# busfahrer.net
KiCad netlist of a schematic drawn in EAGLE
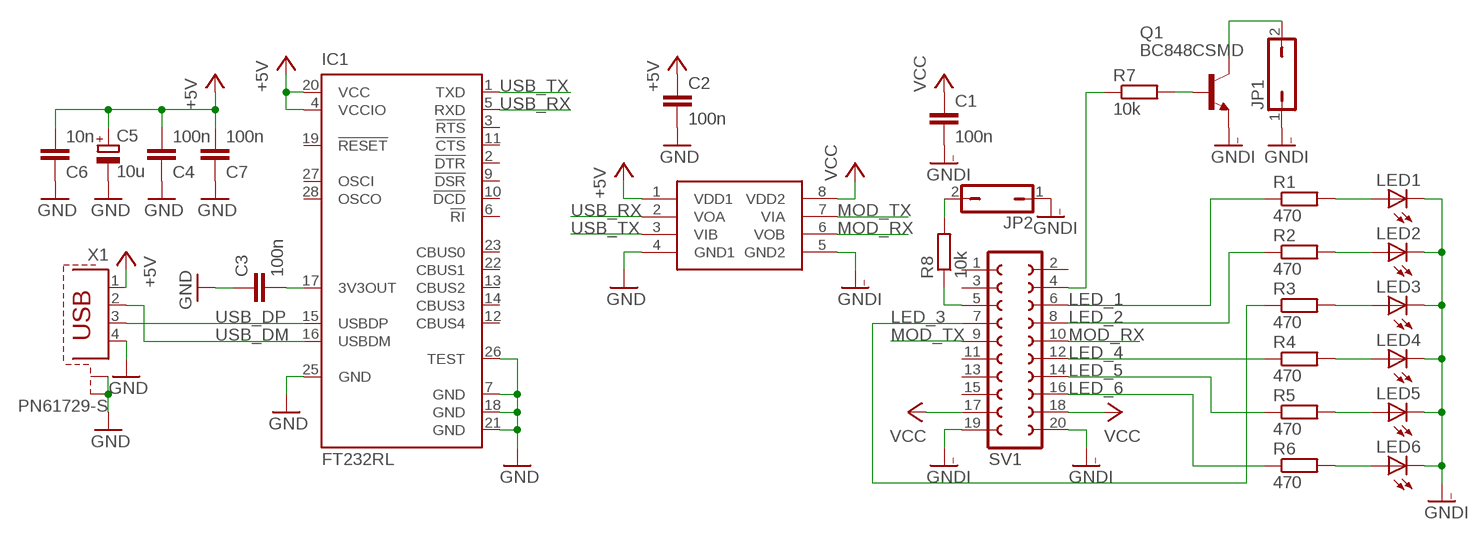
[diagram p0: schematic, sheet 1]

(export (version "E")
  (design (tool "Eeschema 10.0.6"))
  (components
    (comp (ref "C1")
      (value "100n")
      (footprint "eagle-import:C0805")
      (libsource (lib "eagle-import") (part "C-EUC0805"))
    )
    (comp (ref "C2")
      (value "100n")
      (footprint "eagle-import:C0805")
      (libsource (lib "eagle-import") (part "C-EUC0805"))
    )
    (comp (ref "C3")
      (value "100n")
      (footprint "eagle-import:C0805")
      (libsource (lib "eagle-import") (part "C-EUC0805"))
    )
    (comp (ref "C4")
      (value "100n")
      (footprint "eagle-import:C0805")
      (libsource (lib "eagle-import") (part "C-EUC0805"))
    )
    (comp (ref "C5")
      (value "10u")
      (footprint "eagle-import:E1,8-4")
      (libsource (lib "eagle-import") (part "CPOL-EUE1.8-4"))
    )
    (comp (ref "C6")
      (value "10n")
      (footprint "eagle-import:C0805")
      (libsource (lib "eagle-import") (part "C-EUC0805"))
    )
    (comp (ref "C7")
      (value "100n")
      (footprint "eagle-import:C0805")
      (libsource (lib "eagle-import") (part "C-EUC0805"))
    )
    (comp (ref "IC1")
      (value "FT232RL")
      (footprint "eagle-import:SSOP28")
      (libsource (lib "eagle-import") (part "FT232RL"))
    )
    (comp (ref "JP1")
      (value "JP1Q")
      (footprint "eagle-import:JP1")
      (libsource (lib "eagle-import") (part "JP1Q"))
    )
    (comp (ref "JP2")
      (value "JP1Q")
      (footprint "eagle-import:JP1")
      (libsource (lib "eagle-import") (part "JP1Q"))
    )
    (comp (ref "LED1")
      (value "LEDCHIPLED_0805")
      (footprint "eagle-import:CHIPLED_0805")
      (libsource (lib "eagle-import") (part "LEDCHIPLED_0805"))
    )
    (comp (ref "LED2")
      (value "LEDCHIPLED_0805")
      (footprint "eagle-import:CHIPLED_0805")
      (libsource (lib "eagle-import") (part "LEDCHIPLED_0805"))
    )
    (comp (ref "LED3")
      (value "LEDCHIPLED_0805")
      (footprint "eagle-import:CHIPLED_0805")
      (libsource (lib "eagle-import") (part "LEDCHIPLED_0805"))
    )
    (comp (ref "LED4")
      (value "LEDCHIPLED_0805")
      (footprint "eagle-import:CHIPLED_0805")
      (libsource (lib "eagle-import") (part "LEDCHIPLED_0805"))
    )
    (comp (ref "LED5")
      (value "LEDCHIPLED_0805")
      (footprint "eagle-import:CHIPLED_0805")
      (libsource (lib "eagle-import") (part "LEDCHIPLED_0805"))
    )
    (comp (ref "LED6")
      (value "LEDCHIPLED_0805")
      (footprint "eagle-import:CHIPLED_0805")
      (libsource (lib "eagle-import") (part "LEDCHIPLED_0805"))
    )
    (comp (ref "Q1")
      (value "BC848CSMD")
      (footprint "eagle-import:SOT23")
      (libsource (lib "eagle-import") (part "BC848SMDC"))
    )
    (comp (ref "R1")
      (value "470")
      (footprint "eagle-import:R0805")
      (libsource (lib "eagle-import") (part "R-EU_R0805"))
    )
    (comp (ref "R2")
      (value "470")
      (footprint "eagle-import:R0805")
      (libsource (lib "eagle-import") (part "R-EU_R0805"))
    )
    (comp (ref "R3")
      (value "470")
      (footprint "eagle-import:R0805")
      (libsource (lib "eagle-import") (part "R-EU_R0805"))
    )
    (comp (ref "R4")
      (value "470")
      (footprint "eagle-import:R0805")
      (libsource (lib "eagle-import") (part "R-EU_R0805"))
    )
    (comp (ref "R5")
      (value "470")
      (footprint "eagle-import:R0805")
      (libsource (lib "eagle-import") (part "R-EU_R0805"))
    )
    (comp (ref "R6")
      (value "470")
      (footprint "eagle-import:R0805")
      (libsource (lib "eagle-import") (part "R-EU_R0805"))
    )
    (comp (ref "R7")
      (value "10k")
      (footprint "eagle-import:R0805")
      (libsource (lib "eagle-import") (part "R-EU_R0805"))
    )
    (comp (ref "R8")
      (value "10k")
      (footprint "eagle-import:R0805")
      (libsource (lib "eagle-import") (part "R-EU_R0805"))
    )
    (comp (ref "SV1")
      (value "FE10-2")
      (footprint "eagle-import:FE10-2")
      (libsource (lib "eagle-import") (part "FE10-2"))
    )
    (comp (ref "U$1")
      (value "ADUM3211")
      (footprint "eagle-import:SO8")
      (libsource (lib "eagle-import") (part "ADUM3211"))
    )
    (comp (ref "X1")
      (value "PN61729-S")
      (footprint "eagle-import:PN61729-S")
      (libsource (lib "eagle-import") (part "PN61729-S"))
    )
  )
  (nets
    (net (code "1") (name "+5V") (class "Default")
      (node (ref "C2") (pin "1") (pinfunction "1_1") (pintype "passive"))
      (node (ref "C4") (pin "2") (pinfunction "2_2") (pintype "passive"))
      (node (ref "C5") (pin "+") (pinfunction "+_+") (pintype "passive"))
      (node (ref "C6") (pin "2") (pinfunction "2_2") (pintype "passive"))
      (node (ref "C7") (pin "2") (pinfunction "2_2") (pintype "passive"))
      (node (ref "IC1") (pin "20") (pinfunction "VCC_20") (pintype "power_in"))
      (node (ref "IC1") (pin "4") (pinfunction "VCCIO_4") (pintype "power_in"))
      (node (ref "U$1") (pin "1") (pinfunction "VDD1_1") (pintype "bidirectional"))
      (node (ref "X1") (pin "1") (pinfunction "1_1") (pintype "passive"))
    )
    (net (code "2") (name "/LED_1") (class "Default")
      (node (ref "R1") (pin "1") (pinfunction "1_1") (pintype "passive"))
      (node (ref "SV1") (pin "6") (pinfunction "6_6") (pintype "passive"))
    )
    (net (code "3") (name "/LED_2") (class "Default")
      (node (ref "R2") (pin "1") (pinfunction "1_1") (pintype "passive"))
      (node (ref "SV1") (pin "8") (pinfunction "8_8") (pintype "passive"))
    )
    (net (code "4") (name "/LED_3") (class "Default")
      (node (ref "R3") (pin "1") (pinfunction "1_1") (pintype "passive"))
      (node (ref "SV1") (pin "7") (pinfunction "7_7") (pintype "passive"))
    )
    (net (code "5") (name "/LED_4") (class "Default")
      (node (ref "R4") (pin "1") (pinfunction "1_1") (pintype "passive"))
      (node (ref "SV1") (pin "12") (pinfunction "12_12") (pintype "passive"))
    )
    (net (code "6") (name "/LED_5") (class "Default")
      (node (ref "R5") (pin "1") (pinfunction "1_1") (pintype "passive"))
      (node (ref "SV1") (pin "14") (pinfunction "14_14") (pintype "passive"))
    )
    (net (code "7") (name "/LED_6") (class "Default")
      (node (ref "R6") (pin "1") (pinfunction "1_1") (pintype "passive"))
      (node (ref "SV1") (pin "16") (pinfunction "16_16") (pintype "passive"))
    )
    (net (code "8") (name "/MOD_RX") (class "Default")
      (node (ref "SV1") (pin "10") (pinfunction "10_10") (pintype "passive"))
      (node (ref "U$1") (pin "6") (pinfunction "VOB_6") (pintype "bidirectional"))
    )
    (net (code "9") (name "/MOD_TX") (class "Default")
      (node (ref "SV1") (pin "9") (pinfunction "9_9") (pintype "passive"))
      (node (ref "U$1") (pin "7") (pinfunction "VIA_7") (pintype "bidirectional"))
    )
    (net (code "10") (name "/USB_DM") (class "Default")
      (node (ref "IC1") (pin "16") (pinfunction "USBDM_16") (pintype "bidirectional"))
      (node (ref "X1") (pin "2") (pinfunction "2_2") (pintype "passive"))
    )
    (net (code "11") (name "/USB_DP") (class "Default")
      (node (ref "IC1") (pin "15") (pinfunction "USBDP_15") (pintype "bidirectional"))
      (node (ref "X1") (pin "3") (pinfunction "3_3") (pintype "passive"))
    )
    (net (code "12") (name "/USB_RX") (class "Default")
      (node (ref "IC1") (pin "5") (pinfunction "RXD_5") (pintype "input"))
      (node (ref "U$1") (pin "2") (pinfunction "VOA_2") (pintype "bidirectional"))
    )
    (net (code "13") (name "/USB_TX") (class "Default")
      (node (ref "IC1") (pin "1") (pinfunction "TXD_1") (pintype "output"))
      (node (ref "U$1") (pin "3") (pinfunction "VIB_3") (pintype "bidirectional"))
    )
    (net (code "14") (name "GND") (class "Default")
      (node (ref "C2") (pin "2") (pinfunction "2_2") (pintype "passive"))
      (node (ref "C3") (pin "1") (pinfunction "1_1") (pintype "passive"))
      (node (ref "C4") (pin "1") (pinfunction "1_1") (pintype "passive"))
      (node (ref "C5") (pin "-") (pinfunction "-_-") (pintype "passive"))
      (node (ref "C6") (pin "1") (pinfunction "1_1") (pintype "passive"))
      (node (ref "C7") (pin "1") (pinfunction "1_1") (pintype "passive"))
      (node (ref "IC1") (pin "18") (pinfunction "GND_18") (pintype "power_in"))
      (node (ref "IC1") (pin "21") (pinfunction "GND_21") (pintype "power_in"))
      (node (ref "IC1") (pin "25") (pinfunction "GND_25") (pintype "power_in"))
      (node (ref "IC1") (pin "26") (pinfunction "TEST_26") (pintype "input"))
      (node (ref "IC1") (pin "7") (pinfunction "GND_7") (pintype "power_in"))
      (node (ref "U$1") (pin "4") (pinfunction "GND1_4") (pintype "bidirectional"))
      (node (ref "X1") (pin "4") (pinfunction "4_4") (pintype "passive"))
      (node (ref "X1") (pin "S1") (pinfunction "S1_S1") (pintype "passive"))
      (node (ref "X1") (pin "S2") (pinfunction "S2_S2") (pintype "passive"))
    )
    (net (code "15") (name "GNDI") (class "Default")
      (node (ref "C1") (pin "2") (pinfunction "2_2") (pintype "passive"))
      (node (ref "JP1") (pin "1") (pinfunction "1_1") (pintype "passive"))
      (node (ref "JP2") (pin "1") (pinfunction "1_1") (pintype "passive"))
      (node (ref "LED1") (pin "C") (pinfunction "C_C") (pintype "passive"))
      (node (ref "LED2") (pin "C") (pinfunction "C_C") (pintype "passive"))
      (node (ref "LED3") (pin "C") (pinfunction "C_C") (pintype "passive"))
      (node (ref "LED4") (pin "C") (pinfunction "C_C") (pintype "passive"))
      (node (ref "LED5") (pin "C") (pinfunction "C_C") (pintype "passive"))
      (node (ref "LED6") (pin "C") (pinfunction "C_C") (pintype "passive"))
      (node (ref "Q1") (pin "2") (pinfunction "E_2") (pintype "passive"))
      (node (ref "SV1") (pin "19") (pinfunction "19_19") (pintype "passive"))
      (node (ref "SV1") (pin "20") (pinfunction "20_20") (pintype "passive"))
      (node (ref "U$1") (pin "5") (pinfunction "GND2_5") (pintype "bidirectional"))
    )
    (net (code "16") (name "Net-(IC1-3V3OUT)") (class "Default")
      (node (ref "C3") (pin "2") (pinfunction "2_2") (pintype "passive"))
      (node (ref "IC1") (pin "17") (pinfunction "3V3OUT_17") (pintype "output"))
    )
    (net (code "17") (name "Net-(JP2-Pad2)") (class "Default")
      (node (ref "JP2") (pin "2") (pinfunction "2_2") (pintype "passive"))
      (node (ref "R8") (pin "2") (pinfunction "2_2") (pintype "passive"))
    )
    (net (code "18") (name "Net-(LED1-PadA)") (class "Default")
      (node (ref "LED1") (pin "A") (pinfunction "A_A") (pintype "passive"))
      (node (ref "R1") (pin "2") (pinfunction "2_2") (pintype "passive"))
    )
    (net (code "19") (name "Net-(LED2-PadA)") (class "Default")
      (node (ref "LED2") (pin "A") (pinfunction "A_A") (pintype "passive"))
      (node (ref "R2") (pin "2") (pinfunction "2_2") (pintype "passive"))
    )
    (net (code "20") (name "Net-(LED3-PadA)") (class "Default")
      (node (ref "LED3") (pin "A") (pinfunction "A_A") (pintype "passive"))
      (node (ref "R3") (pin "2") (pinfunction "2_2") (pintype "passive"))
    )
    (net (code "21") (name "Net-(LED4-PadA)") (class "Default")
      (node (ref "LED4") (pin "A") (pinfunction "A_A") (pintype "passive"))
      (node (ref "R4") (pin "2") (pinfunction "2_2") (pintype "passive"))
    )
    (net (code "22") (name "Net-(LED5-PadA)") (class "Default")
      (node (ref "LED5") (pin "A") (pinfunction "A_A") (pintype "passive"))
      (node (ref "R5") (pin "2") (pinfunction "2_2") (pintype "passive"))
    )
    (net (code "23") (name "Net-(LED6-PadA)") (class "Default")
      (node (ref "LED6") (pin "A") (pinfunction "A_A") (pintype "passive"))
      (node (ref "R6") (pin "2") (pinfunction "2_2") (pintype "passive"))
    )
    (net (code "24") (name "Net-(Q1-B)") (class "Default")
      (node (ref "Q1") (pin "1") (pinfunction "B_1") (pintype "passive"))
      (node (ref "R7") (pin "2") (pinfunction "2_2") (pintype "passive"))
    )
    (net (code "25") (name "Net-(Q1-C)") (class "Default")
      (node (ref "JP1") (pin "2") (pinfunction "2_2") (pintype "passive"))
      (node (ref "Q1") (pin "3") (pinfunction "C_3") (pintype "passive"))
    )
    (net (code "26") (name "Net-(R7-Pad1)") (class "Default")
      (node (ref "R7") (pin "1") (pinfunction "1_1") (pintype "passive"))
      (node (ref "SV1") (pin "4") (pinfunction "4_4") (pintype "passive"))
    )
    (net (code "27") (name "Net-(R8-Pad1)") (class "Default")
      (node (ref "R8") (pin "1") (pinfunction "1_1") (pintype "passive"))
      (node (ref "SV1") (pin "5") (pinfunction "5_5") (pintype "passive"))
    )
    (net (code "28") (name "VCC") (class "Default")
      (node (ref "C1") (pin "1") (pinfunction "1_1") (pintype "passive"))
      (node (ref "SV1") (pin "17") (pinfunction "17_17") (pintype "passive"))
      (node (ref "SV1") (pin "18") (pinfunction "18_18") (pintype "passive"))
      (node (ref "U$1") (pin "8") (pinfunction "VDD2_8") (pintype "bidirectional"))
    )
    (net (code "29") (name "unconnected-(IC1-CBUS0-Pad23)") (class "Default")
      (node (ref "IC1") (pin "23") (pinfunction "CBUS0_23") (pintype "bidirectional"))
    )
    (net (code "30") (name "unconnected-(IC1-CBUS1-Pad22)") (class "Default")
      (node (ref "IC1") (pin "22") (pinfunction "CBUS1_22") (pintype "bidirectional"))
    )
    (net (code "31") (name "unconnected-(IC1-CBUS2-Pad13)") (class "Default")
      (node (ref "IC1") (pin "13") (pinfunction "CBUS2_13") (pintype "bidirectional"))
    )
    (net (code "32") (name "unconnected-(IC1-CBUS3-Pad14)") (class "Default")
      (node (ref "IC1") (pin "14") (pinfunction "CBUS3_14") (pintype "bidirectional"))
    )
    (net (code "33") (name "unconnected-(IC1-CBUS4-Pad12)") (class "Default")
      (node (ref "IC1") (pin "12") (pinfunction "CBUS4_12") (pintype "bidirectional"))
    )
    (net (code "34") (name "unconnected-(IC1-OSCI-Pad27)") (class "Default")
      (node (ref "IC1") (pin "27") (pinfunction "OSCI_27") (pintype "input"))
    )
    (net (code "35") (name "unconnected-(IC1-OSCO-Pad28)") (class "Default")
      (node (ref "IC1") (pin "28") (pinfunction "OSCO_28") (pintype "output"))
    )
    (net (code "36") (name "unconnected-(IC1-~{CTS}-Pad11)") (class "Default")
      (node (ref "IC1") (pin "11") (pinfunction "~{CTS}_11") (pintype "input"))
    )
    (net (code "37") (name "unconnected-(IC1-~{DCD}-Pad10)") (class "Default")
      (node (ref "IC1") (pin "10") (pinfunction "~{DCD}_10") (pintype "input"))
    )
    (net (code "38") (name "unconnected-(IC1-~{DSR}-Pad9)") (class "Default")
      (node (ref "IC1") (pin "9") (pinfunction "~{DSR}_9") (pintype "input"))
    )
    (net (code "39") (name "unconnected-(IC1-~{DTR}-Pad2)") (class "Default")
      (node (ref "IC1") (pin "2") (pinfunction "~{DTR}_2") (pintype "output"))
    )
    (net (code "40") (name "unconnected-(IC1-~{RESET}-Pad19)") (class "Default")
      (node (ref "IC1") (pin "19") (pinfunction "~{RESET}_19") (pintype "input"))
    )
    (net (code "41") (name "unconnected-(IC1-~{RI}-Pad6)") (class "Default")
      (node (ref "IC1") (pin "6") (pinfunction "~{RI}_6") (pintype "input"))
    )
    (net (code "42") (name "unconnected-(IC1-~{RTS}-Pad3)") (class "Default")
      (node (ref "IC1") (pin "3") (pinfunction "~{RTS}_3") (pintype "output"))
    )
    (net (code "43") (name "unconnected-(SV1-Pad1)") (class "Default")
      (node (ref "SV1") (pin "1") (pinfunction "1_1") (pintype "passive"))
    )
    (net (code "44") (name "unconnected-(SV1-Pad2)") (class "Default")
      (node (ref "SV1") (pin "2") (pinfunction "2_2") (pintype "passive"))
    )
    (net (code "45") (name "unconnected-(SV1-Pad3)") (class "Default")
      (node (ref "SV1") (pin "3") (pinfunction "3_3") (pintype "passive"))
    )
    (net (code "46") (name "unconnected-(SV1-Pad11)") (class "Default")
      (node (ref "SV1") (pin "11") (pinfunction "11_11") (pintype "passive"))
    )
    (net (code "47") (name "unconnected-(SV1-Pad13)") (class "Default")
      (node (ref "SV1") (pin "13") (pinfunction "13_13") (pintype "passive"))
    )
    (net (code "48") (name "unconnected-(SV1-Pad15)") (class "Default")
      (node (ref "SV1") (pin "15") (pinfunction "15_15") (pintype "passive"))
    )
  )
)
